# schematic.net
KiCad netlist of a schematic drawn in EAGLE
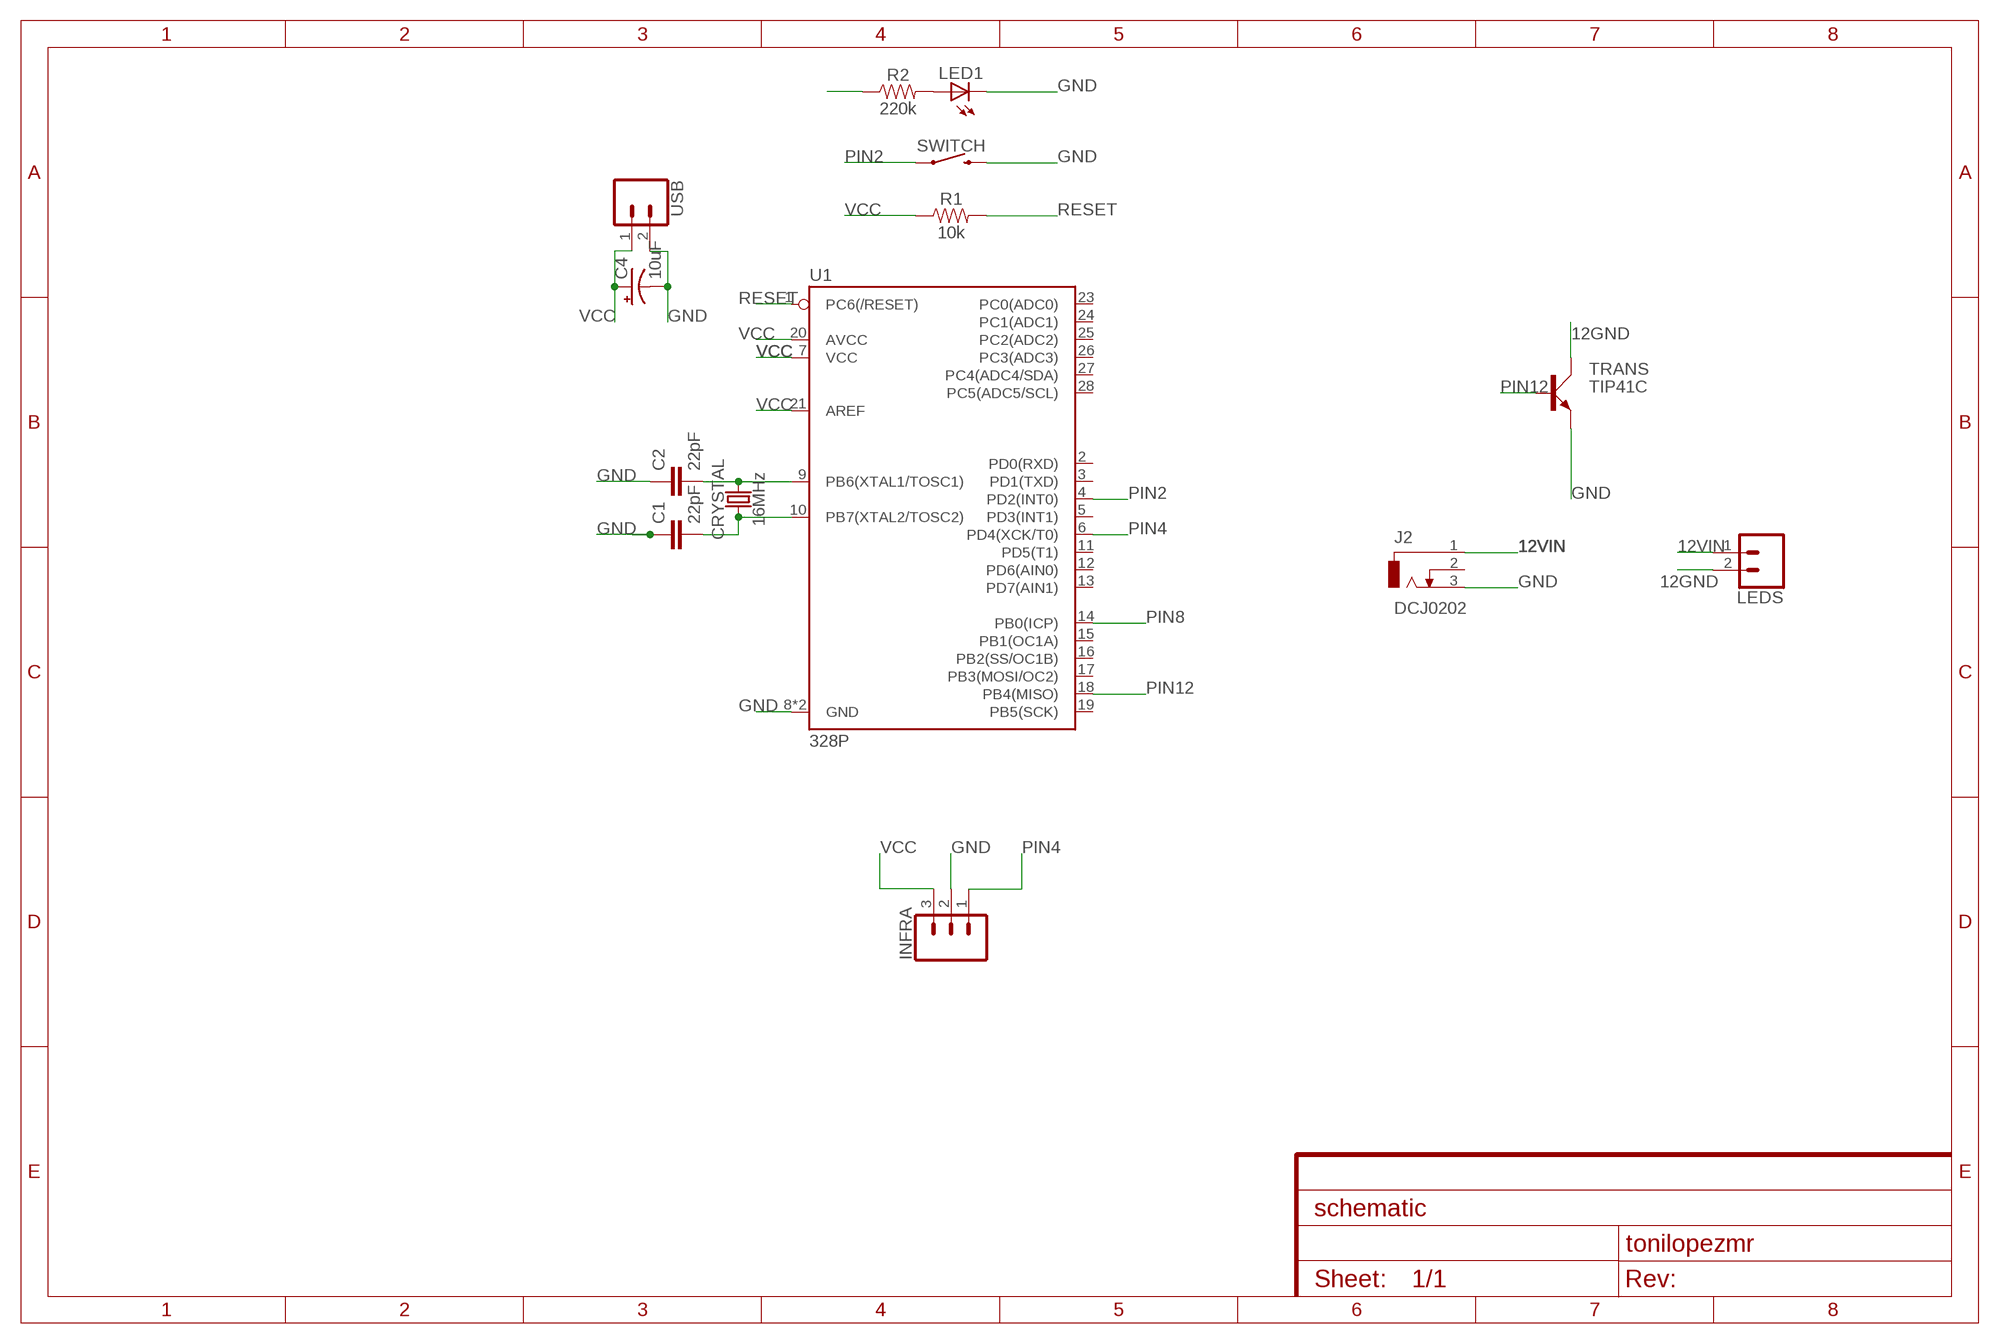
[diagram p0: schematic, sheet 1]

(export (version "E")
  (design (tool "Eeschema 10.0.6"))
  (components
    (comp (ref "C1")
      (value "22pF")
      (footprint "eagle-import:CAP-PTH-2.54")
      (libsource (lib "eagle-import") (part "22PF-PTH-2.54MM-200V-5%"))
    )
    (comp (ref "C2")
      (value "22pF")
      (footprint "eagle-import:CAP-PTH-2.54")
      (libsource (lib "eagle-import") (part "22PF-PTH-2.54MM-200V-5%"))
    )
    (comp (ref "C4")
      (value "10uF")
      (footprint "eagle-import:CPOL-RADIAL-2.5MM-5MM")
      (libsource (lib "eagle-import") (part "10UF-POLAR-RADIAL-2.5MM-25V-20%"))
    )
    (comp (ref "CRYSTAL")
      (value "16MHz")
      (footprint "eagle-import:HC49US")
      (libsource (lib "eagle-import") (part "CRYSTAL-16MHZPTH-HC49US"))
    )
    (comp (ref "INFRA")
      (value "455-1750-1-ND")
      (footprint "eagle-import:1X03")
      (libsource (lib "eagle-import") (part "CONN_03"))
    )
    (comp (ref "J2")
      (value "DCJ0202")
      (footprint "eagle-import:DCJ0202")
      (libsource (lib "eagle-import") (part "DCJ0202"))
    )
    (comp (ref "LED1")
      (value "LED5MM")
      (footprint "eagle-import:LED5MM")
      (libsource (lib "eagle-import") (part "LED5MM"))
    )
    (comp (ref "LEDS")
      (value "CONN_02")
      (footprint "eagle-import:1X02")
      (libsource (lib "eagle-import") (part "CONN_02"))
    )
    (comp (ref "R1")
      (value "10k")
      (footprint "eagle-import:AXIAL-0.3")
      (libsource (lib "eagle-import") (part "10KOHM-HORIZ-1/4W-1%"))
    )
    (comp (ref "R2")
      (value "220k")
      (footprint "eagle-import:AXIAL-0.3")
      (libsource (lib "eagle-import") (part "10KOHM-HORIZ-1/4W-1%"))
    )
    (comp (ref "SWITCH")
      (value "MOMENTARY-SWITCH-SPST-PTH-6.0MM")
      (footprint "eagle-import:TACTILE_SWITCH_PTH_6.0MM")
      (libsource (lib "eagle-import") (part "MOMENTARY-SWITCH-SPST-PTH-6.0MM"))
    )
    (comp (ref "TRANS")
      (value "TIP41C")
      (footprint "eagle-import:TO220AV")
      (libsource (lib "eagle-import") (part "TIP41C"))
    )
    (comp (ref "U1")
      (value "328P")
      (footprint "eagle-import:DIP28")
      (libsource (lib "eagle-import") (part "ATMEGA328P_PDIP"))
    )
    (comp (ref "USB")
      (value "CONN_02")
      (footprint "eagle-import:1X02")
      (libsource (lib "eagle-import") (part "CONN_02"))
    )
  )
  (nets
    (net (code "1") (name "/12GND") (class "Default")
      (node (ref "LEDS") (pin "2") (pinfunction "2_2") (pintype "passive"))
      (node (ref "TRANS") (pin "C") (pinfunction "C_C") (pintype "passive"))
    )
    (net (code "2") (name "/12VIN") (class "Default")
      (node (ref "J2") (pin "1") (pinfunction "1_1") (pintype "passive"))
      (node (ref "LEDS") (pin "1") (pinfunction "1_1") (pintype "passive"))
    )
    (net (code "3") (name "/GND") (class "Default")
      (node (ref "C1") (pin "1") (pinfunction "1_1") (pintype "passive"))
      (node (ref "C2") (pin "1") (pinfunction "1_1") (pintype "passive"))
      (node (ref "C4") (pin "2") (pinfunction "-_2") (pintype "passive"))
      (node (ref "INFRA") (pin "2") (pinfunction "2_2") (pintype "passive"))
      (node (ref "J2") (pin "3") (pinfunction "3_3") (pintype "passive"))
      (node (ref "LED1") (pin "K") (pinfunction "C_K") (pintype "passive"))
      (node (ref "SWITCH") (pin "3") (pinfunction "2_3") (pintype "passive"))
      (node (ref "TRANS") (pin "E") (pinfunction "E_E") (pintype "passive"))
      (node (ref "U1") (pin "22") (pinfunction "GND_22") (pintype "bidirectional"))
      (node (ref "U1") (pin "8") (pinfunction "GND_8") (pintype "bidirectional"))
      (node (ref "USB") (pin "2") (pinfunction "2_2") (pintype "passive"))
    )
    (net (code "4") (name "/PIN2") (class "Default")
      (node (ref "SWITCH") (pin "1") (pinfunction "1_1") (pintype "passive"))
      (node (ref "U1") (pin "4") (pinfunction "PD2(INT0)_4") (pintype "bidirectional"))
    )
    (net (code "5") (name "/PIN4") (class "Default")
      (node (ref "INFRA") (pin "1") (pinfunction "1_1") (pintype "passive"))
      (node (ref "U1") (pin "6") (pinfunction "PD4(XCK/T0)_6") (pintype "bidirectional"))
    )
    (net (code "6") (name "/PIN8") (class "Default")
      (node (ref "R2") (pin "P$1") (pinfunction "1_P$1") (pintype "passive"))
      (node (ref "U1") (pin "14") (pinfunction "PB0(ICP)_14") (pintype "bidirectional"))
    )
    (net (code "7") (name "/PIN12") (class "Default")
      (node (ref "TRANS") (pin "B") (pinfunction "B_B") (pintype "passive"))
      (node (ref "U1") (pin "18") (pinfunction "PB4(MISO)_18") (pintype "bidirectional"))
    )
    (net (code "8") (name "/RESET") (class "Default")
      (node (ref "R1") (pin "P$2") (pinfunction "2_P$2") (pintype "passive"))
      (node (ref "U1") (pin "1") (pinfunction "PC6(/RESET)_1") (pintype "bidirectional"))
    )
    (net (code "9") (name "/VCC") (class "Default")
      (node (ref "C4") (pin "1") (pinfunction "+_1") (pintype "passive"))
      (node (ref "INFRA") (pin "3") (pinfunction "3_3") (pintype "passive"))
      (node (ref "R1") (pin "P$1") (pinfunction "1_P$1") (pintype "passive"))
      (node (ref "U1") (pin "20") (pinfunction "AVCC_20") (pintype "bidirectional"))
      (node (ref "U1") (pin "21") (pinfunction "AREF_21") (pintype "bidirectional"))
      (node (ref "U1") (pin "7") (pinfunction "VCC_7") (pintype "bidirectional"))
      (node (ref "USB") (pin "1") (pinfunction "1_1") (pintype "passive"))
    )
    (net (code "10") (name "Net-(R2-2)") (class "Default")
      (node (ref "LED1") (pin "A") (pinfunction "A_A") (pintype "passive"))
      (node (ref "R2") (pin "P$2") (pinfunction "2_P$2") (pintype "passive"))
    )
    (net (code "11") (name "Net-(U1-PB6(XTAL1{slash}TOSC1))") (class "Default")
      (node (ref "C2") (pin "2") (pinfunction "2_2") (pintype "passive"))
      (node (ref "CRYSTAL") (pin "2") (pinfunction "2_2") (pintype "passive"))
      (node (ref "U1") (pin "9") (pinfunction "PB6(XTAL1/TOSC1)_9") (pintype "bidirectional"))
    )
    (net (code "12") (name "Net-(U1-PB7(XTAL2{slash}TOSC2))") (class "Default")
      (node (ref "C1") (pin "2") (pinfunction "2_2") (pintype "passive"))
      (node (ref "CRYSTAL") (pin "1") (pinfunction "1_1") (pintype "passive"))
      (node (ref "U1") (pin "10") (pinfunction "PB7(XTAL2/TOSC2)_10") (pintype "bidirectional"))
    )
    (net (code "13") (name "unconnected-(J2-Pad2)") (class "Default")
      (node (ref "J2") (pin "2") (pinfunction "2_2") (pintype "passive"))
    )
    (net (code "14") (name "unconnected-(U1-PB1(OC1A)-Pad15)") (class "Default")
      (node (ref "U1") (pin "15") (pinfunction "PB1(OC1A)_15") (pintype "bidirectional"))
    )
    (net (code "15") (name "unconnected-(U1-PB2(SS{slash}OC1B)-Pad16)") (class "Default")
      (node (ref "U1") (pin "16") (pinfunction "PB2(SS/OC1B)_16") (pintype "bidirectional"))
    )
    (net (code "16") (name "unconnected-(U1-PB3(MOSI{slash}OC2)-Pad17)") (class "Default")
      (node (ref "U1") (pin "17") (pinfunction "PB3(MOSI/OC2)_17") (pintype "bidirectional"))
    )
    (net (code "17") (name "unconnected-(U1-PB5(SCK)-Pad19)") (class "Default")
      (node (ref "U1") (pin "19") (pinfunction "PB5(SCK)_19") (pintype "bidirectional"))
    )
    (net (code "18") (name "unconnected-(U1-PC0(ADC0)-Pad23)") (class "Default")
      (node (ref "U1") (pin "23") (pinfunction "PC0(ADC0)_23") (pintype "bidirectional"))
    )
    (net (code "19") (name "unconnected-(U1-PC1(ADC1)-Pad24)") (class "Default")
      (node (ref "U1") (pin "24") (pinfunction "PC1(ADC1)_24") (pintype "bidirectional"))
    )
    (net (code "20") (name "unconnected-(U1-PC2(ADC2)-Pad25)") (class "Default")
      (node (ref "U1") (pin "25") (pinfunction "PC2(ADC2)_25") (pintype "bidirectional"))
    )
    (net (code "21") (name "unconnected-(U1-PC3(ADC3)-Pad26)") (class "Default")
      (node (ref "U1") (pin "26") (pinfunction "PC3(ADC3)_26") (pintype "bidirectional"))
    )
    (net (code "22") (name "unconnected-(U1-PC4(ADC4{slash}SDA)-Pad27)") (class "Default")
      (node (ref "U1") (pin "27") (pinfunction "PC4(ADC4/SDA)_27") (pintype "bidirectional"))
    )
    (net (code "23") (name "unconnected-(U1-PC5(ADC5{slash}SCL)-Pad28)") (class "Default")
      (node (ref "U1") (pin "28") (pinfunction "PC5(ADC5/SCL)_28") (pintype "bidirectional"))
    )
    (net (code "24") (name "unconnected-(U1-PD0(RXD)-Pad2)") (class "Default")
      (node (ref "U1") (pin "2") (pinfunction "PD0(RXD)_2") (pintype "bidirectional"))
    )
    (net (code "25") (name "unconnected-(U1-PD1(TXD)-Pad3)") (class "Default")
      (node (ref "U1") (pin "3") (pinfunction "PD1(TXD)_3") (pintype "bidirectional"))
    )
    (net (code "26") (name "unconnected-(U1-PD3(INT1)-Pad5)") (class "Default")
      (node (ref "U1") (pin "5") (pinfunction "PD3(INT1)_5") (pintype "bidirectional"))
    )
    (net (code "27") (name "unconnected-(U1-PD5(T1)-Pad11)") (class "Default")
      (node (ref "U1") (pin "11") (pinfunction "PD5(T1)_11") (pintype "bidirectional"))
    )
    (net (code "28") (name "unconnected-(U1-PD6(AIN0)-Pad12)") (class "Default")
      (node (ref "U1") (pin "12") (pinfunction "PD6(AIN0)_12") (pintype "bidirectional"))
    )
    (net (code "29") (name "unconnected-(U1-PD7(AIN1)-Pad13)") (class "Default")
      (node (ref "U1") (pin "13") (pinfunction "PD7(AIN1)_13") (pintype "bidirectional"))
    )
  )
)
